# 03-MCU.net
KiCad netlist of a schematic drawn in Altium Designer
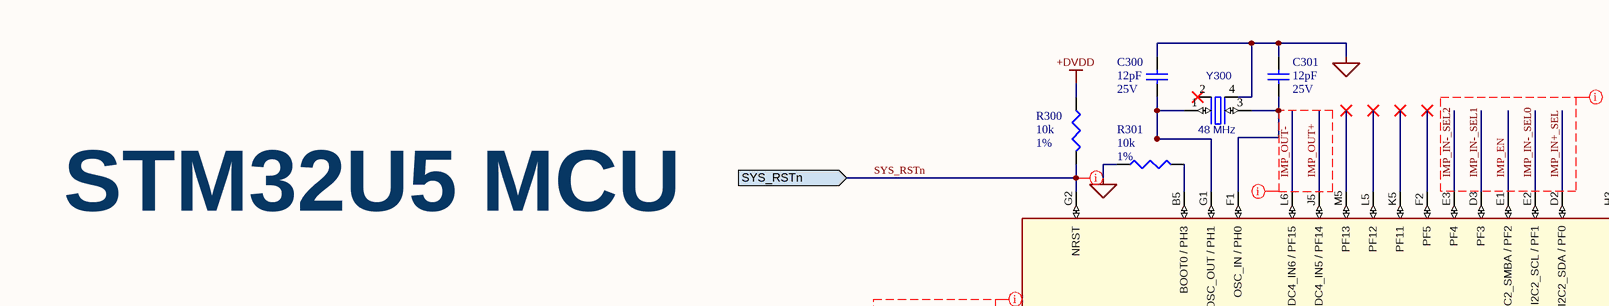
[diagram p0: 03-MCU.SchDoc, top left]
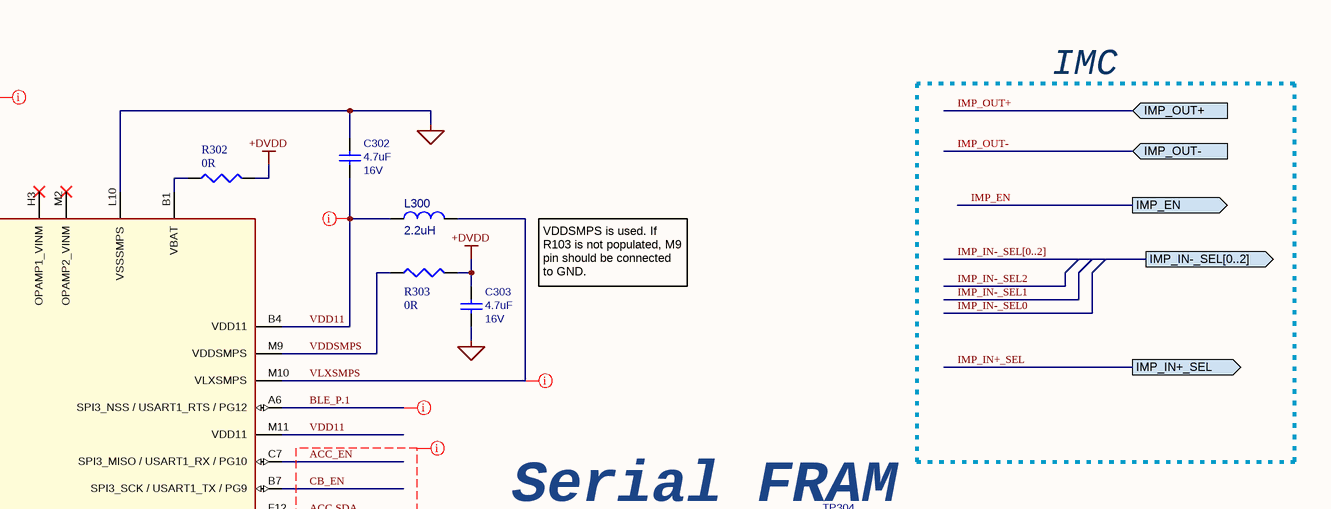
[diagram p1: 03-MCU.SchDoc, top right]
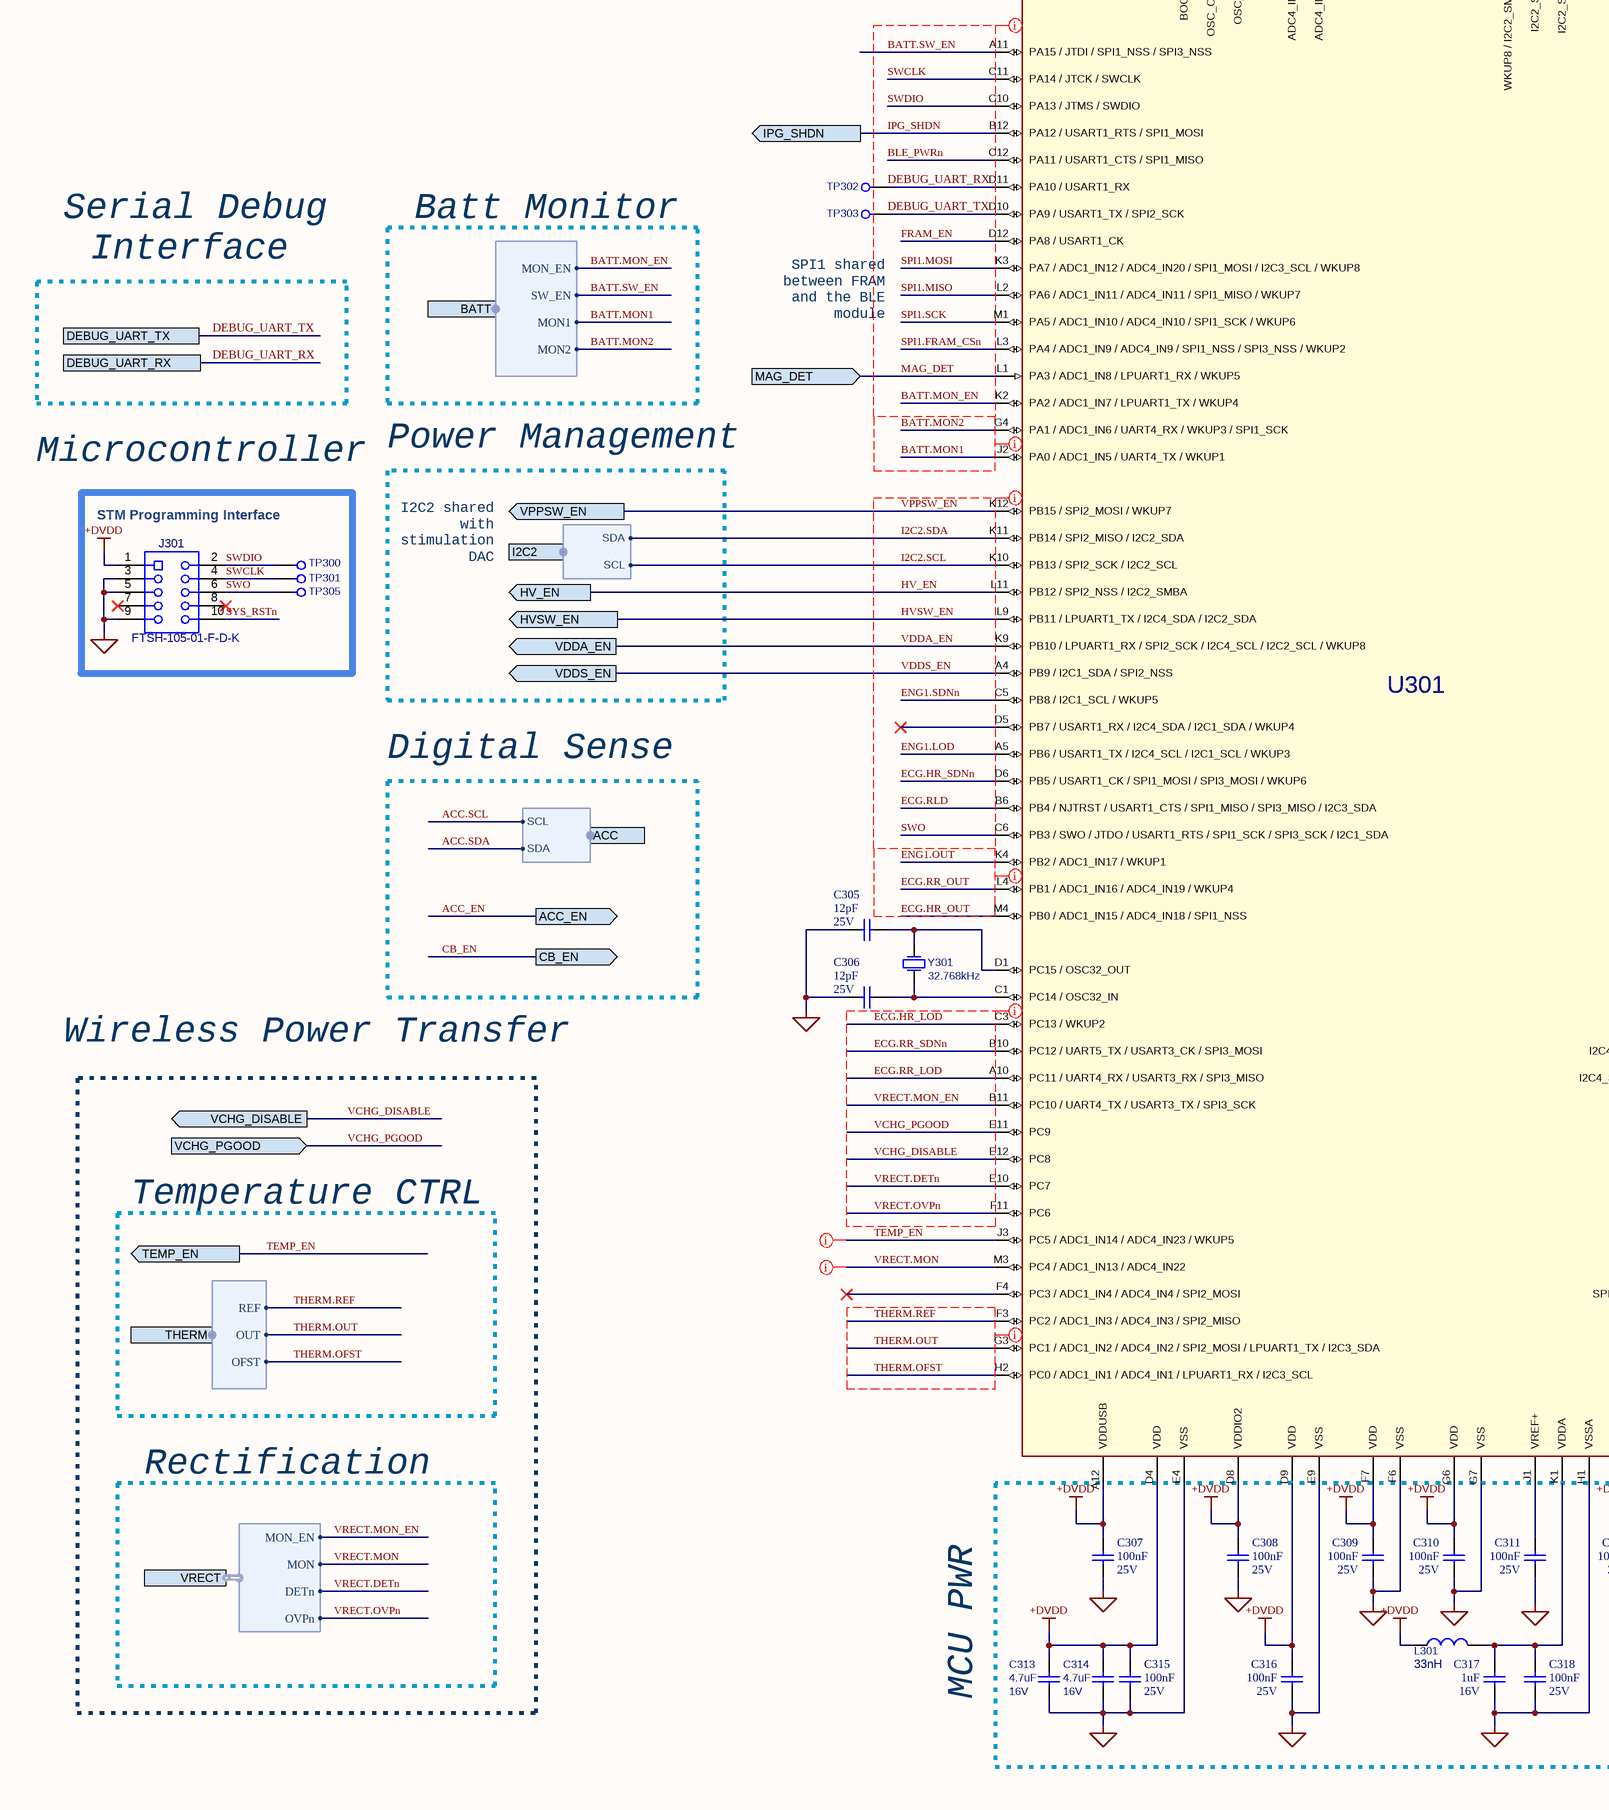
[diagram p2: 03-MCU.SchDoc, bottom left]
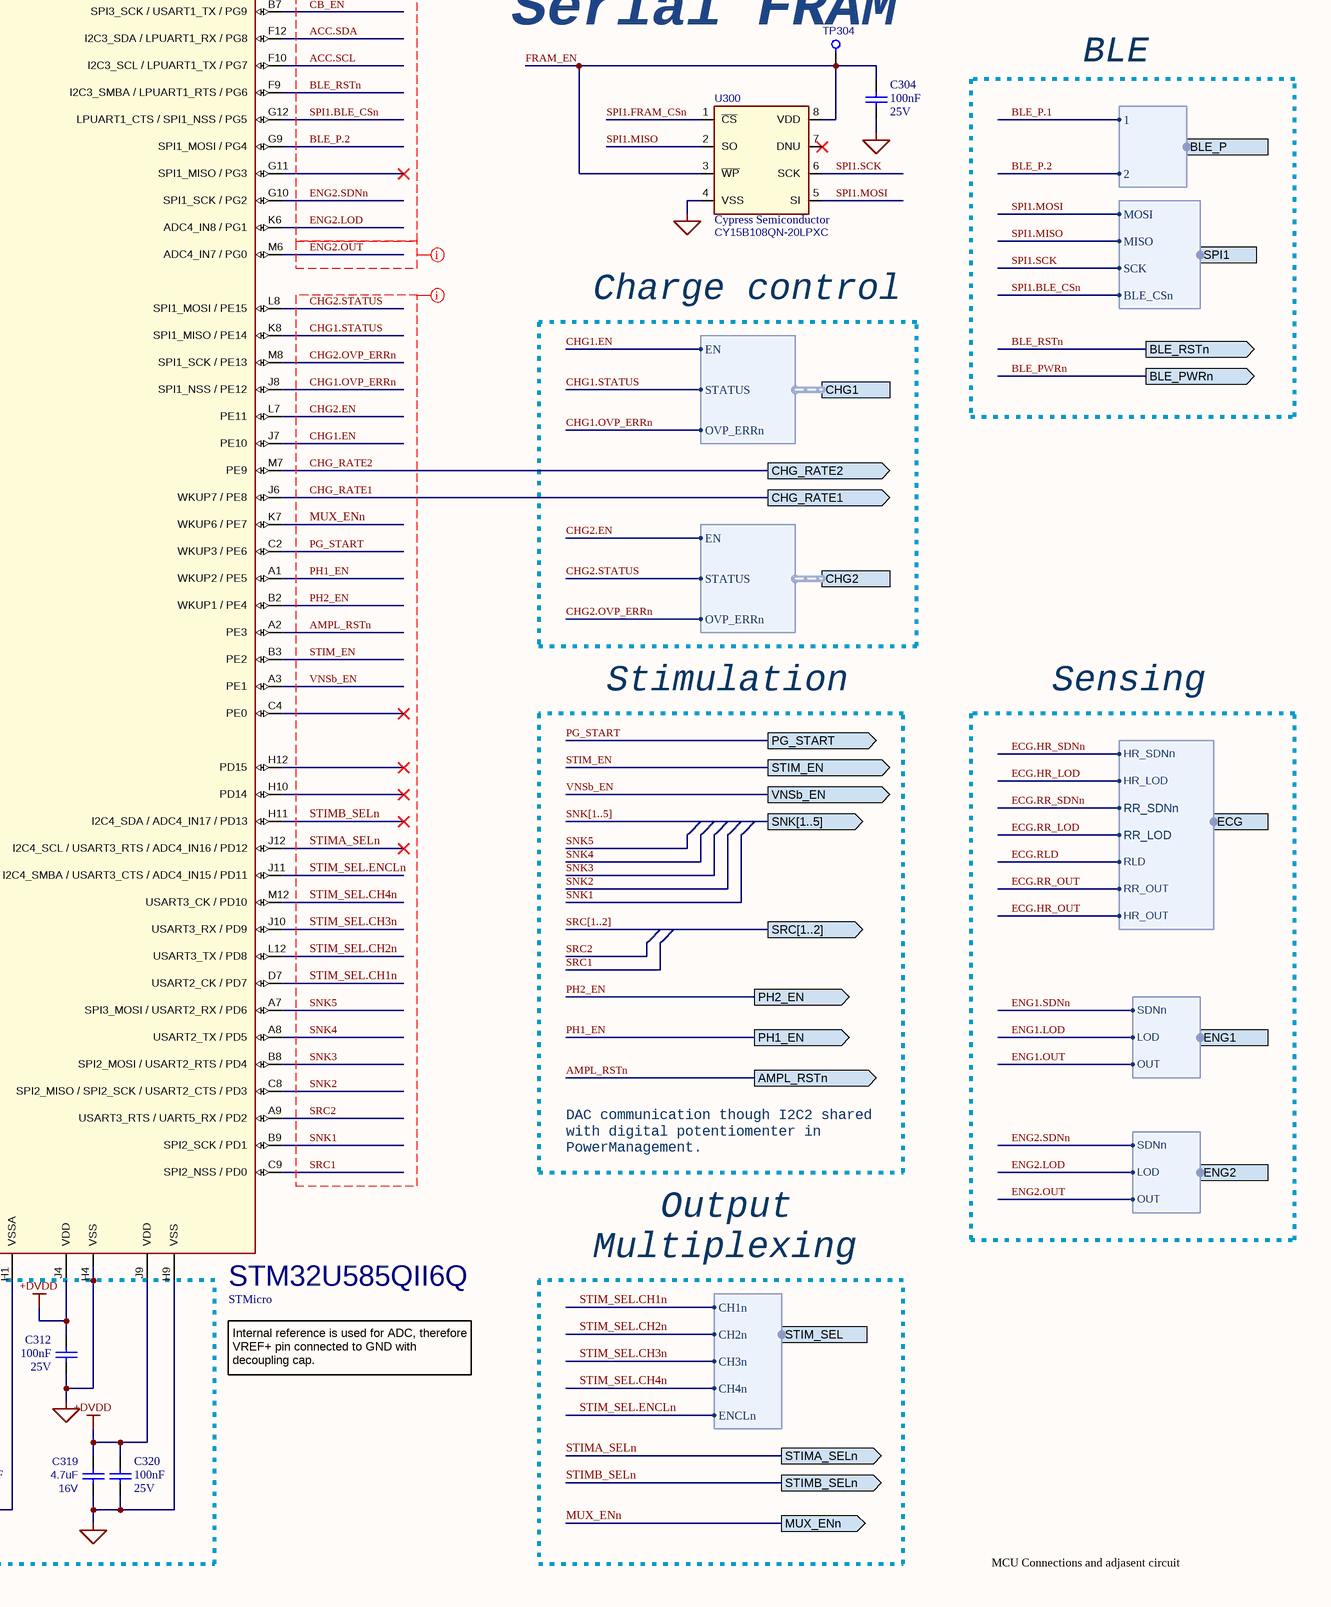
[diagram p3: 03-MCU.SchDoc, bottom right]

(export (version "E")
  (design (tool "Eeschema 10.0.6"))
  (components
    (comp (ref "C300")
      (value "12pF")
      (footprint "C0201_C")
      (fields
        (field (name "MANUFACTURER") "Murata")
        (field (name "MANUFACTURER PART NUMBER") "GRM0335C1E120JA01D")
        (field (name "RATED DC VOLTAGE (URDC)") "25V")
      )
      (libsource (lib "MP-LIBRARY") (part "GRM0335C1E120JA01D"))
    )
    (comp (ref "C301")
      (value "12pF")
      (footprint "C0201_C")
      (fields
        (field (name "MANUFACTURER") "Murata")
        (field (name "MANUFACTURER PART NUMBER") "GRM0335C1E120JA01D")
        (field (name "RATED DC VOLTAGE (URDC)") "25V")
      )
      (libsource (lib "MP-LIBRARY") (part "GRM0335C1E120JA01D"))
    )
    (comp (ref "C302")
      (value "4.7uF")
      (footprint "CAP0603_REDUCED")
      (description "Capacitor, 4.7uF, X5R, 16V, 10%, 0603, Implant-grade")
      (fields
        (field (name "MANUFACTURER") "Murata")
        (field (name "RATING") "16V")
        (field (name "MANUFACTURER PART NUMBER") "GRM188R61C475KE11")
      )
      (libsource (lib "MP-LIBRARY") (part "GRM188R61C475KE11"))
    )
    (comp (ref "C303")
      (value "4.7uF")
      (footprint "CAP0603_REDUCED")
      (description "Capacitor, 4.7uF, X5R, 16V, 10%, 0603, Implant-grade")
      (fields
        (field (name "MANUFACTURER") "Murata")
        (field (name "RATING") "16V")
        (field (name "MANUFACTURER PART NUMBER") "GRM188R61C475KE11")
      )
      (libsource (lib "MP-LIBRARY") (part "GRM188R61C475KE11"))
    )
    (comp (ref "C304")
      (value "100nF")
      (footprint "C0201_C")
      (fields
        (field (name "MANUFACTURER") "Murata")
        (field (name "MANUFACTURER PART NUMBER") "GRM033R61E104KE14J")
        (field (name "RATED DC VOLTAGE (URDC)") "25V")
      )
      (libsource (lib "MP-LIBRARY") (part "GRM033R61E104KE14J"))
    )
    (comp (ref "C305")
      (value "12pF")
      (footprint "C0201_C")
      (fields
        (field (name "MANUFACTURER") "Murata")
        (field (name "MANUFACTURER PART NUMBER") "GRM0335C1E120JA01D")
        (field (name "RATED DC VOLTAGE (URDC)") "25V")
      )
      (libsource (lib "MP-LIBRARY") (part "GRM0335C1E120JA01D"))
    )
    (comp (ref "C306")
      (value "12pF")
      (footprint "C0201_C")
      (fields
        (field (name "MANUFACTURER") "Murata")
        (field (name "MANUFACTURER PART NUMBER") "GRM0335C1E120JA01D")
        (field (name "RATED DC VOLTAGE (URDC)") "25V")
      )
      (libsource (lib "MP-LIBRARY") (part "GRM0335C1E120JA01D"))
    )
    (comp (ref "C307")
      (value "100nF")
      (footprint "C0201_C")
      (fields
        (field (name "MANUFACTURER") "Murata")
        (field (name "MANUFACTURER PART NUMBER") "GRM033R61E104KE14J")
        (field (name "RATED DC VOLTAGE (URDC)") "25V")
      )
      (libsource (lib "MP-LIBRARY") (part "GRM033R61E104KE14J"))
    )
    (comp (ref "C308")
      (value "100nF")
      (footprint "C0201_C")
      (fields
        (field (name "MANUFACTURER") "Murata")
        (field (name "MANUFACTURER PART NUMBER") "GRM033R61E104KE14J")
        (field (name "RATED DC VOLTAGE (URDC)") "25V")
      )
      (libsource (lib "MP-LIBRARY") (part "GRM033R61E104KE14J"))
    )
    (comp (ref "C309")
      (value "100nF")
      (footprint "C0201_C")
      (fields
        (field (name "MANUFACTURER") "Murata")
        (field (name "MANUFACTURER PART NUMBER") "GRM033R61E104KE14J")
        (field (name "RATED DC VOLTAGE (URDC)") "25V")
      )
      (libsource (lib "MP-LIBRARY") (part "GRM033R61E104KE14J"))
    )
    (comp (ref "C310")
      (value "100nF")
      (footprint "C0201_C")
      (fields
        (field (name "MANUFACTURER") "Murata")
        (field (name "MANUFACTURER PART NUMBER") "GRM033R61E104KE14J")
        (field (name "RATED DC VOLTAGE (URDC)") "25V")
      )
      (libsource (lib "MP-LIBRARY") (part "GRM033R61E104KE14J"))
    )
    (comp (ref "C311")
      (value "100nF")
      (footprint "C0201_C")
      (fields
        (field (name "MANUFACTURER") "Murata")
        (field (name "MANUFACTURER PART NUMBER") "GRM033R61E104KE14J")
        (field (name "RATED DC VOLTAGE (URDC)") "25V")
      )
      (libsource (lib "MP-LIBRARY") (part "GRM033R61E104KE14J"))
    )
    (comp (ref "C312")
      (value "100nF")
      (footprint "C0201_C")
      (fields
        (field (name "MANUFACTURER") "Murata")
        (field (name "MANUFACTURER PART NUMBER") "GRM033R61E104KE14J")
        (field (name "RATED DC VOLTAGE (URDC)") "25V")
      )
      (libsource (lib "MP-LIBRARY") (part "GRM033R61E104KE14J"))
    )
    (comp (ref "C313")
      (value "4.7uF")
      (footprint "CAP0603_REDUCED")
      (description "Capacitor, 4.7uF, X5R, 16V, 10%, 0603, Implant-grade")
      (fields
        (field (name "MANUFACTURER") "Murata")
        (field (name "RATING") "16V")
        (field (name "MANUFACTURER PART NUMBER") "GRM188R61C475KE11")
      )
      (libsource (lib "MP-LIBRARY") (part "GRM188R61C475KE11"))
    )
    (comp (ref "C314")
      (value "4.7uF")
      (footprint "CAP0603_REDUCED")
      (description "Capacitor, 4.7uF, X5R, 16V, 10%, 0603, Implant-grade")
      (fields
        (field (name "MANUFACTURER") "Murata")
        (field (name "RATING") "16V")
        (field (name "MANUFACTURER PART NUMBER") "GRM188R61C475KE11")
      )
      (libsource (lib "MP-LIBRARY") (part "GRM188R61C475KE11"))
    )
    (comp (ref "C315")
      (value "100nF")
      (footprint "C0201_C")
      (fields
        (field (name "MANUFACTURER") "Murata")
        (field (name "MANUFACTURER PART NUMBER") "GRM033R61E104KE14J")
        (field (name "RATED DC VOLTAGE (URDC)") "25V")
      )
      (libsource (lib "MP-LIBRARY") (part "GRM033R61E104KE14J"))
    )
    (comp (ref "C316")
      (value "100nF")
      (footprint "C0201_C")
      (fields
        (field (name "MANUFACTURER") "Murata")
        (field (name "MANUFACTURER PART NUMBER") "GRM033R61E104KE14J")
        (field (name "RATED DC VOLTAGE (URDC)") "25V")
      )
      (libsource (lib "MP-LIBRARY") (part "GRM033R61E104KE14J"))
    )
    (comp (ref "C317")
      (value "1uF")
      (footprint "C0201_C")
      (fields
        (field (name "MANUFACTURER") "Murata")
        (field (name "MANUFACTURER PART NUMBER") "GRM033R61C105ME15D")
        (field (name "RATED DC VOLTAGE (URDC)") "16V")
      )
      (libsource (lib "MP-LIBRARY") (part "GRM033R61C105ME15D"))
    )
    (comp (ref "C318")
      (value "100nF")
      (footprint "C0201_C")
      (fields
        (field (name "MANUFACTURER") "Murata")
        (field (name "MANUFACTURER PART NUMBER") "GRM033R61E104KE14J")
        (field (name "RATED DC VOLTAGE (URDC)") "25V")
      )
      (libsource (lib "MP-LIBRARY") (part "GRM033R61E104KE14J"))
    )
    (comp (ref "C319")
      (value "4.7uF")
      (footprint "CAP0603_REDUCED")
      (description "Capacitor, 4.7uF, X5R, 16V, 10%, 0603, Implant-grade")
      (fields
        (field (name "MANUFACTURER") "Murata")
        (field (name "RATING") "16V")
        (field (name "MANUFACTURER PART NUMBER") "GRM188R61C475KE11")
      )
      (libsource (lib "MP-LIBRARY") (part "GRM188R61C475KE11"))
    )
    (comp (ref "C320")
      (value "100nF")
      (footprint "C0201_C")
      (fields
        (field (name "MANUFACTURER") "Murata")
        (field (name "MANUFACTURER PART NUMBER") "GRM033R61E104KE14J")
        (field (name "RATED DC VOLTAGE (URDC)") "25V")
      )
      (libsource (lib "MP-LIBRARY") (part "GRM033R61E104KE14J"))
    )
    (comp (ref "J301")
      (value "FTSH-105-01-F-D-K")
      (footprint "SAMTEC_FTSH-105-01-XXX-D-K")
      (description "Connector, 1.27 mm, 2x5, Male, TH")
      (fields (field (name "MANUFACTURER") "Samtec"))
      (libsource (lib "MP-LIBRARY") (part "FTSH-105-01-F-D-K"))
    )
    (comp (ref "L300")
      (value "2.2uH")
      (footprint "TDK_VLS252010HBX-1")
      (description "Inductor, 2.2uH, 1.76A, 1008")
      (fields
        (field (name "MANUFACTURER") "TDK")
        (field (name "MANUFACTURER PART NUMBER") "VLS252010HBX-2R2M-1")
      )
      (libsource (lib "MP-LIBRARY") (part "VLS252010HBX-2R2M-1"))
    )
    (comp (ref "L301")
      (value "33nH")
      (footprint "L0402_C")
      (description "Inductor, Unshielded, 33nH, 350mA, 0402")
      (fields
        (field (name "MANUFACTURER") "Murata")
        (field (name "MANUFACTURER PART NUMBER") "LQG15HS33NJ02D")
      )
      (libsource (lib "MP-LIBRARY") (part "LQG15HS33NJ02D"))
    )
    (comp (ref "R300")
      (value "10k")
      (footprint "R0201_C")
      (fields
        (field (name "MANUFACTURER") "Vishay")
        (field (name "MANUFACTURER PART NUMBER") "CRCW020110K0FNED")
        (field (name "TOLERANCE") "1%")
        (field (name "POWER") "50mW")
      )
      (libsource (lib "MP-LIBRARY") (part "CRCW020110K0FNED"))
    )
    (comp (ref "R301")
      (value "10k")
      (footprint "R0201_C")
      (fields
        (field (name "MANUFACTURER") "Vishay")
        (field (name "MANUFACTURER PART NUMBER") "CRCW020110K0FNED")
        (field (name "TOLERANCE") "1%")
        (field (name "POWER") "50mW")
      )
      (libsource (lib "MP-LIBRARY") (part "CRCW020110K0FNED"))
    )
    (comp (ref "R302")
      (value "0R")
      (footprint "R0201_C")
      (description "Fixed Resistor, Metal Glaze/thick Film, 0.05W, 0ohm, Surface Mount, 0201")
      (fields
        (field (name "MANUFACTURER") "Vishay")
        (field (name "MANUFACTURER PART NUMBER") "CRCW02010000Z0ED")
      )
      (libsource (lib "MP-LIBRARY") (part "CRCW02010000Z0ED"))
    )
    (comp (ref "R303")
      (value "0R")
      (footprint "R0201_C")
      (description "Fixed Resistor, Metal Glaze/thick Film, 0.05W, 0ohm, Surface Mount, 0201")
      (fields
        (field (name "MANUFACTURER") "Vishay")
        (field (name "MANUFACTURER PART NUMBER") "CRCW02010000Z0ED")
      )
      (libsource (lib "MP-LIBRARY") (part "CRCW02010000Z0ED"))
    )
    (comp (ref "TP300")
      (value "Test Point")
      (footprint "testpad_0.9mm")
      (description "Test pad, 0.90mm circular pad")
      (libsource (lib "MP-LIBRARY") (part "Test Point"))
    )
    (comp (ref "TP301")
      (value "Test Point")
      (footprint "testpad_0.9mm")
      (description "Test pad, 0.90mm circular pad")
      (libsource (lib "MP-LIBRARY") (part "Test Point"))
    )
    (comp (ref "TP302")
      (value "Test Point")
      (footprint "testpad_0.9mm")
      (description "Test pad, 0.90mm circular pad")
      (libsource (lib "MP-LIBRARY") (part "Test Point"))
    )
    (comp (ref "TP303")
      (value "Test Point")
      (footprint "testpad_0.9mm")
      (description "Test pad, 0.90mm circular pad")
      (libsource (lib "MP-LIBRARY") (part "Test Point"))
    )
    (comp (ref "TP304")
      (value "Test Point")
      (footprint "testpad_0.9mm")
      (description "Test pad, 0.90mm circular pad")
      (libsource (lib "MP-LIBRARY") (part "Test Point"))
    )
    (comp (ref "TP305")
      (value "Test Point")
      (footprint "testpad_0.9mm")
      (description "Test pad, 0.90mm circular pad")
      (libsource (lib "MP-LIBRARY") (part "Test Point"))
    )
    (comp (ref "U300")
      (value "CY15B108QN-20LPXC")
      (footprint "CY_002-18131_GQFN8")
      (description "FRAM, 8 Mbit (1024k x 8), SPI, 1.8-3.6V, QFN-8")
      (fields (field (name "MANUFACTURER") "Cypress Semiconductor"))
      (libsource (lib "MP-LIBRARY") (part "CY15B108QN-20LPXC"))
    )
    (comp (ref "U301")
      (value "STM32U585QII6Q")
      (footprint "STM_UFBGA132")
      (fields (field (name "MANUFACTURER") "STMicro"))
      (libsource (lib "MP-LIBRARY") (part "STM32U585QII6Q"))
    )
    (comp (ref "Y300")
      (value "48 MHz")
      (footprint "XTAL_ECS-SMD-CRYSTAL-10-48-CKY-TR")
      (description "48 MHz Â±10ppm Crystal 10pF 100 Ohms 4-SMD, No Lead")
      (fields
        (field (name "MANUFACTURER") "ECS Inc.")
        (field (name "MANUFACTURER PART NUMBER") "ECS-480-10-48-CKY-TR")
      )
      (libsource (lib "MP-LIBRARY") (part "ECS-480-10-48-CKY-TR"))
    )
    (comp (ref "Y301")
      (value "32.768kHz")
      (footprint "MICROCRYSTAL_CC8V-T1A")
      (description "CRYSTAL 32.7680KHZ 6PF SMD")
      (fields
        (field (name "MANUFACTURER") "Micro Crystal")
        (field (name "MANUFACTURER PART NUMBER") "CM8V-T1A-32.768KHZ-6PF-20PPM-TA-QC")
      )
      (libsource (lib "MP-LIBRARY") (part "CM8V-T1A-32.768KHZ-6PF-20PPM-TA-QC"))
    )
  )
  (nets
    (net (code "13") (name "+DVDD") (class "Default")
      (node (ref "C303") (pin "1") (pinfunction "1_1") (pintype "passive"))
      (node (ref "C307") (pin "2") (pinfunction "2_2") (pintype "passive"))
      (node (ref "C308") (pin "2") (pinfunction "2_2") (pintype "passive"))
      (node (ref "C309") (pin "2") (pinfunction "2_2") (pintype "passive"))
      (node (ref "C310") (pin "2") (pinfunction "2_2") (pintype "passive"))
      (node (ref "C312") (pin "2") (pinfunction "2_2") (pintype "passive"))
      (node (ref "C313") (pin "1") (pinfunction "1_1") (pintype "passive"))
      (node (ref "C314") (pin "1") (pinfunction "1_1") (pintype "passive"))
      (node (ref "C315") (pin "2") (pinfunction "2_2") (pintype "passive"))
      (node (ref "C316") (pin "2") (pinfunction "2_2") (pintype "passive"))
      (node (ref "C319") (pin "1") (pinfunction "1_1") (pintype "passive"))
      (node (ref "C320") (pin "2") (pinfunction "2_2") (pintype "passive"))
      (node (ref "J301") (pin "1") (pinfunction "1_1") (pintype "passive"))
      (node (ref "L301") (pin "1") (pinfunction "1_1") (pintype "passive"))
      (node (ref "R300") (pin "1") (pinfunction "1_1") (pintype "passive"))
      (node (ref "R302") (pin "2") (pinfunction "2_2") (pintype "passive"))
      (node (ref "R303") (pin "2") (pinfunction "2_2") (pintype "passive"))
      (node (ref "U301") (pin "A12") (pinfunction "VDDUSB_A12") (pintype "power_in"))
      (node (ref "U301") (pin "D4") (pinfunction "VDD_D4") (pintype "power_in"))
      (node (ref "U301") (pin "D8") (pinfunction "VDDIO2_D8") (pintype "power_in"))
      (node (ref "U301") (pin "D9") (pinfunction "VDD_D9") (pintype "power_in"))
      (node (ref "U301") (pin "F7") (pinfunction "VDD_F7") (pintype "power_in"))
      (node (ref "U301") (pin "G6") (pinfunction "VDD_G6") (pintype "power_in"))
      (node (ref "U301") (pin "J4") (pinfunction "VDD_J4") (pintype "power_in"))
      (node (ref "U301") (pin "J9") (pinfunction "VDD_J9") (pintype "power_in"))
    )
    (net (code "14") (name "/ACC.SCL") (class "Default")
      (node (ref "U301") (pin "F10") (pinfunction "I2C3_SCL_/_LPUART1_TX_/_PG7_F10") (pintype "bidirectional"))
    )
    (net (code "15") (name "/ACC.SDA") (class "Default")
      (node (ref "U301") (pin "F12") (pinfunction "I2C3_SDA_/_LPUART1_RX_/_PG8_F12") (pintype "bidirectional"))
    )
    (net (code "16") (name "/ACC_EN") (class "Default")
      (node (ref "U301") (pin "C7") (pinfunction "SPI3_MISO_/_USART1_RX_/_PG10_C7") (pintype "bidirectional"))
    )
    (net (code "17") (name "/AMPL_RSTn") (class "Default")
      (node (ref "U301") (pin "A2") (pinfunction "PE3_A2") (pintype "bidirectional"))
    )
    (net (code "18") (name "/BATT.MON1") (class "Default")
      (node (ref "U301") (pin "J2") (pinfunction "PA0_/_ADC1_IN5_/_UART4_TX_/_WKUP1_J2") (pintype "bidirectional"))
    )
    (net (code "19") (name "/BATT.MON2") (class "Default")
      (node (ref "U301") (pin "G4") (pinfunction "PA1_/_ADC1_IN6_/_UART4_RX_/_WKUP3_/_SPI1_SCK_G4") (pintype "bidirectional"))
    )
    (net (code "20") (name "/BATT.MON_EN") (class "Default")
      (node (ref "U301") (pin "K2") (pinfunction "PA2_/_ADC1_IN7_/_LPUART1_TX_/_WKUP4_K2") (pintype "bidirectional"))
    )
    (net (code "21") (name "/BATT.SW_EN") (class "Default")
      (node (ref "U301") (pin "A11") (pinfunction "PA15_/_JTDI_/_SPI1_NSS_/_SPI3_NSS_A11") (pintype "bidirectional"))
    )
    (net (code "22") (name "/BLE_P.1") (class "Default")
      (node (ref "U301") (pin "A6") (pinfunction "SPI3_NSS_/_USART1_RTS_/_PG12_A6") (pintype "bidirectional"))
    )
    (net (code "23") (name "/BLE_P.2") (class "Default")
      (node (ref "U301") (pin "G9") (pinfunction "SPI1_MOSI_/_PG4_G9") (pintype "bidirectional"))
    )
    (net (code "24") (name "/BLE_PWRn") (class "Default")
      (node (ref "U301") (pin "C12") (pinfunction "PA11_/_USART1_CTS_/_SPI1_MISO_C12") (pintype "bidirectional"))
    )
    (net (code "25") (name "/BLE_RSTn") (class "Default")
      (node (ref "U301") (pin "F9") (pinfunction "I2C3_SMBA_/_LPUART1_RTS_/_PG6_F9") (pintype "bidirectional"))
    )
    (net (code "26") (name "/CB_EN") (class "Default")
      (node (ref "U301") (pin "B7") (pinfunction "SPI3_SCK_/_USART1_TX_/_PG9_B7") (pintype "bidirectional"))
    )
    (net (code "27") (name "/CHG1.EN") (class "Default")
      (node (ref "U301") (pin "J7") (pinfunction "PE10_J7") (pintype "bidirectional"))
    )
    (net (code "28") (name "/CHG1.OVP_ERRn") (class "Default")
      (node (ref "U301") (pin "J8") (pinfunction "SPI1_NSS_/_PE12_J8") (pintype "bidirectional"))
    )
    (net (code "29") (name "/CHG1.STATUS") (class "Default")
      (node (ref "U301") (pin "K8") (pinfunction "SPI1_MISO_/_PE14_K8") (pintype "bidirectional"))
    )
    (net (code "30") (name "/CHG2.EN") (class "Default")
      (node (ref "U301") (pin "L7") (pinfunction "PE11_L7") (pintype "bidirectional"))
    )
    (net (code "31") (name "/CHG2.OVP_ERRn") (class "Default")
      (node (ref "U301") (pin "M8") (pinfunction "SPI1_SCK_/_PE13_M8") (pintype "bidirectional"))
    )
    (net (code "32") (name "/CHG2.STATUS") (class "Default")
      (node (ref "U301") (pin "L8") (pinfunction "SPI1_MOSI_/_PE15_L8") (pintype "bidirectional"))
    )
    (net (code "33") (name "/CHG_RATE1") (class "Default")
      (node (ref "U301") (pin "J6") (pinfunction "WKUP7_/_PE8_J6") (pintype "bidirectional"))
    )
    (net (code "34") (name "/CHG_RATE2") (class "Default")
      (node (ref "U301") (pin "M7") (pinfunction "PE9_M7") (pintype "bidirectional"))
    )
    (net (code "35") (name "/DEBUG_UART_RX") (class "Default")
      (node (ref "TP302") (pin "1") (pinfunction "1_1") (pintype "passive"))
      (node (ref "U301") (pin "D11") (pinfunction "PA10_/_USART1_RX_D11") (pintype "bidirectional"))
    )
    (net (code "36") (name "/DEBUG_UART_TX") (class "Default")
      (node (ref "TP303") (pin "1") (pinfunction "1_1") (pintype "passive"))
      (node (ref "U301") (pin "D10") (pinfunction "PA9_/_USART1_TX_/_SPI2_SCK_D10") (pintype "bidirectional"))
    )
    (net (code "37") (name "/ECG.HR_LOD") (class "Default")
      (node (ref "U301") (pin "C3") (pinfunction "PC13_/_WKUP2_C3") (pintype "bidirectional"))
    )
    (net (code "38") (name "/ECG.HR_OUT") (class "Default")
      (node (ref "U301") (pin "M4") (pinfunction "PB0_/_ADC1_IN15_/_ADC4_IN18_/_SPI1_NSS_M4") (pintype "bidirectional"))
    )
    (net (code "39") (name "/ECG.HR_SDNn") (class "Default")
      (node (ref "U301") (pin "D6") (pinfunction "PB5_/_USART1_CK_/_SPI1_MOSI_/_SPI3_MOSI_/_WKUP6_D6") (pintype "bidirectional"))
    )
    (net (code "40") (name "/ECG.RLD") (class "Default")
      (node (ref "U301") (pin "B6") (pinfunction "PB4_/_NJTRST_/_USART1_CTS_/_SPI1_MISO_/_SPI3_MISO_/_I2C3_SDA_B6") (pintype "bidirectional"))
    )
    (net (code "41") (name "/ECG.RR_LOD") (class "Default")
      (node (ref "U301") (pin "A10") (pinfunction "PC11_/_UART4_RX_/_USART3_RX_/_SPI3_MISO_A10") (pintype "bidirectional"))
    )
    (net (code "42") (name "/ECG.RR_OUT") (class "Default")
      (node (ref "U301") (pin "L4") (pinfunction "PB1_/_ADC1_IN16_/_ADC4_IN19_/_WKUP4_L4") (pintype "bidirectional"))
    )
    (net (code "43") (name "/ECG.RR_SDNn") (class "Default")
      (node (ref "U301") (pin "B10") (pinfunction "PC12_/_UART5_TX_/_USART3_CK_/_SPI3_MOSI_B10") (pintype "bidirectional"))
    )
    (net (code "44") (name "/ENG1.LOD") (class "Default")
      (node (ref "U301") (pin "A5") (pinfunction "PB6_/_USART1_TX_/_I2C4_SCL_/_I2C1_SCL_/_WKUP3_A5") (pintype "bidirectional"))
    )
    (net (code "45") (name "/ENG1.OUT") (class "Default")
      (node (ref "U301") (pin "K4") (pinfunction "PB2_/_ADC1_IN17_/_WKUP1_K4") (pintype "bidirectional"))
    )
    (net (code "46") (name "/ENG1.SDNn") (class "Default")
      (node (ref "U301") (pin "C5") (pinfunction "PB8_/_I2C1_SCL_/_WKUP5_C5") (pintype "bidirectional"))
    )
    (net (code "47") (name "/ENG2.LOD") (class "Default")
      (node (ref "U301") (pin "K6") (pinfunction "ADC4_IN8_/_PG1_K6") (pintype "bidirectional"))
    )
    (net (code "48") (name "/ENG2.OUT") (class "Default")
      (node (ref "U301") (pin "M6") (pinfunction "ADC4_IN7_/_PG0_M6") (pintype "bidirectional"))
    )
    (net (code "49") (name "/ENG2.SDNn") (class "Default")
      (node (ref "U301") (pin "G10") (pinfunction "SPI1_SCK_/_PG2_G10") (pintype "bidirectional"))
    )
    (net (code "50") (name "/FRAM_EN") (class "Default")
      (node (ref "C304") (pin "2") (pinfunction "2_2") (pintype "passive"))
      (node (ref "TP304") (pin "1") (pinfunction "1_1") (pintype "passive"))
      (node (ref "U300") (pin "3") (pinfunction "~{WP}_3") (pintype "passive"))
      (node (ref "U300") (pin "8") (pinfunction "VDD_8") (pintype "power_in"))
      (node (ref "U301") (pin "D12") (pinfunction "PA8_/_USART1_CK_D12") (pintype "bidirectional"))
    )
    (net (code "51") (name "/HVSW_EN") (class "Default")
      (node (ref "U301") (pin "L9") (pinfunction "PB11_/_LPUART1_TX_/_I2C4_SDA_/_I2C2_SDA_L9") (pintype "bidirectional"))
    )
    (net (code "52") (name "/HV_EN") (class "Default")
      (node (ref "U301") (pin "L11") (pinfunction "PB12_/_SPI2_NSS_/_I2C2_SMBA_L11") (pintype "bidirectional"))
    )
    (net (code "53") (name "/I2C2.SCL") (class "Default")
      (node (ref "U301") (pin "K10") (pinfunction "PB13_/_SPI2_SCK_/_I2C2_SCL_K10") (pintype "bidirectional"))
    )
    (net (code "54") (name "/I2C2.SDA") (class "Default")
      (node (ref "U301") (pin "K11") (pinfunction "PB14_/_SPI2_MISO_/_I2C2_SDA_K11") (pintype "bidirectional"))
    )
    (net (code "55") (name "/IMP_EN") (class "Default")
      (node (ref "U301") (pin "E1") (pinfunction "WKUP8_/_I2C2_SMBA_/_PF2_E1") (pintype "bidirectional"))
    )
    (net (code "56") (name "/IMP_IN+_SEL") (class "Default")
      (node (ref "U301") (pin "D2") (pinfunction "I2C2_SDA_/_PF0_D2") (pintype "bidirectional"))
    )
    (net (code "57") (name "/IMP_IN-_SEL0") (class "Default")
      (node (ref "U301") (pin "E2") (pinfunction "I2C2_SCL_/_PF1_E2") (pintype "bidirectional"))
    )
    (net (code "58") (name "/IMP_IN-_SEL1") (class "Default")
      (node (ref "U301") (pin "D3") (pinfunction "PF3_D3") (pintype "bidirectional"))
    )
    (net (code "59") (name "/IMP_IN-_SEL2") (class "Default")
      (node (ref "U301") (pin "E3") (pinfunction "PF4_E3") (pintype "bidirectional"))
    )
    (net (code "61") (name "/IMP_OUT+") (class "Default")
      (node (ref "U301") (pin "J5") (pinfunction "ADC4_IN5_/_PF14_J5") (pintype "bidirectional"))
    )
    (net (code "62") (name "/IMP_OUT-") (class "Default")
      (node (ref "U301") (pin "L6") (pinfunction "ADC4_IN6_/_PF15_L6") (pintype "bidirectional"))
    )
    (net (code "63") (name "/IPG_SHDN") (class "Default")
      (node (ref "U301") (pin "B12") (pinfunction "PA12_/_USART1_RTS_/_SPI1_MOSI_B12") (pintype "bidirectional"))
    )
    (net (code "64") (name "/MAG_DET") (class "Default")
      (node (ref "U301") (pin "L1") (pinfunction "PA3_/_ADC1_IN8_/_LPUART1_RX_/_WKUP5_L1") (pintype "input"))
    )
    (net (code "65") (name "/MUX_ENn") (class "Default")
      (node (ref "U301") (pin "K7") (pinfunction "WKUP6_/_PE7_K7") (pintype "bidirectional"))
    )
    (net (code "66") (name "/PG_START") (class "Default")
      (node (ref "U301") (pin "C2") (pinfunction "WKUP3_/_PE6_C2") (pintype "bidirectional"))
    )
    (net (code "67") (name "/PH1_EN") (class "Default")
      (node (ref "U301") (pin "A1") (pinfunction "WKUP2_/_PE5_A1") (pintype "bidirectional"))
    )
    (net (code "68") (name "/PH2_EN") (class "Default")
      (node (ref "U301") (pin "B2") (pinfunction "WKUP1_/_PE4_B2") (pintype "bidirectional"))
    )
    (net (code "69") (name "/SNK1") (class "Default")
      (node (ref "U301") (pin "B9") (pinfunction "SPI2_SCK_/_PD1_B9") (pintype "bidirectional"))
    )
    (net (code "70") (name "/SNK2") (class "Default")
      (node (ref "U301") (pin "C8") (pinfunction "SPI2_MISO_/_SPI2_SCK_/_USART2_CTS_/_PD3_C8") (pintype "bidirectional"))
    )
    (net (code "71") (name "/SNK3") (class "Default")
      (node (ref "U301") (pin "B8") (pinfunction "SPI2_MOSI_/_USART2_RTS_/_PD4_B8") (pintype "bidirectional"))
    )
    (net (code "72") (name "/SNK4") (class "Default")
      (node (ref "U301") (pin "A8") (pinfunction "USART2_TX_/_PD5_A8") (pintype "bidirectional"))
    )
    (net (code "73") (name "/SNK5") (class "Default")
      (node (ref "U301") (pin "A7") (pinfunction "SPI3_MOSI_/_USART2_RX_/_PD6_A7") (pintype "bidirectional"))
    )
    (net (code "75") (name "/SPI1.BLE_CSn") (class "Default")
      (node (ref "U301") (pin "G12") (pinfunction "LPUART1_CTS_/_SPI1_NSS_/_PG5_G12") (pintype "bidirectional"))
    )
    (net (code "76") (name "/SPI1.FRAM_CSn") (class "Default")
      (node (ref "U300") (pin "1") (pinfunction "~{CS}_1") (pintype "passive"))
      (node (ref "U301") (pin "L3") (pinfunction "PA4_/_ADC1_IN9_/_ADC4_IN9_/_SPI1_NSS_/_SPI3_NSS_/_WKUP2_L3") (pintype "bidirectional"))
    )
    (net (code "77") (name "/SPI1.MISO") (class "Default")
      (node (ref "U300") (pin "2") (pinfunction "SO_2") (pintype "passive"))
      (node (ref "U301") (pin "L2") (pinfunction "PA6_/_ADC1_IN11_/_ADC4_IN11_/_SPI1_MISO_/_WKUP7_L2") (pintype "bidirectional"))
    )
    (net (code "78") (name "/SPI1.MOSI") (class "Default")
      (node (ref "U300") (pin "5") (pinfunction "SI_5") (pintype "passive"))
      (node (ref "U301") (pin "K3") (pinfunction "PA7_/_ADC1_IN12_/_ADC4_IN20_/_SPI1_MOSI_/_I2C3_SCL_/_WKUP8_K3") (pintype "bidirectional"))
    )
    (net (code "79") (name "/SPI1.SCK") (class "Default")
      (node (ref "U300") (pin "6") (pinfunction "SCK_6") (pintype "passive"))
      (node (ref "U301") (pin "M1") (pinfunction "PA5_/_ADC1_IN10_/_ADC4_IN10_/_SPI1_SCK_/_WKUP6_M1") (pintype "bidirectional"))
    )
    (net (code "80") (name "/SRC1") (class "Default")
      (node (ref "U301") (pin "C9") (pinfunction "SPI2_NSS_/_PD0_C9") (pintype "bidirectional"))
    )
    (net (code "81") (name "/SRC2") (class "Default")
      (node (ref "U301") (pin "A9") (pinfunction "USART3_RTS_/_UART5_RX_/_PD2_A9") (pintype "bidirectional"))
    )
    (net (code "83") (name "/STIMA_SELn") (class "Default")
      (node (ref "U301") (pin "J12") (pinfunction "I2C4_SCL_/_USART3_RTS_/_ADC4_IN16_/_PD12_J12") (pintype "bidirectional+no_connect"))
    )
    (net (code "84") (name "/STIMB_SELn") (class "Default")
      (node (ref "U301") (pin "H11") (pinfunction "I2C4_SDA_/_ADC4_IN17_/_PD13_H11") (pintype "bidirectional+no_connect"))
    )
    (net (code "85") (name "/STIM_EN") (class "Default")
      (node (ref "U301") (pin "B3") (pinfunction "PE2_B3") (pintype "bidirectional"))
    )
    (net (code "86") (name "/STIM_SEL.CH1n") (class "Default")
      (node (ref "U301") (pin "D7") (pinfunction "USART2_CK_/_PD7_D7") (pintype "bidirectional"))
    )
    (net (code "87") (name "/STIM_SEL.CH2n") (class "Default")
      (node (ref "U301") (pin "L12") (pinfunction "USART3_TX_/_PD8_L12") (pintype "bidirectional"))
    )
    (net (code "88") (name "/STIM_SEL.CH3n") (class "Default")
      (node (ref "U301") (pin "J10") (pinfunction "USART3_RX_/_PD9_J10") (pintype "bidirectional"))
    )
    (net (code "89") (name "/STIM_SEL.CH4n") (class "Default")
      (node (ref "U301") (pin "M12") (pinfunction "USART3_CK_/_PD10_M12") (pintype "bidirectional"))
    )
    (net (code "90") (name "/STIM_SEL.ENCLn") (class "Default")
      (node (ref "U301") (pin "J11") (pinfunction "I2C4_SMBA_/_USART3_CTS_/_ADC4_IN15_/_PD11_J11") (pintype "bidirectional"))
    )
    (net (code "91") (name "/SWCLK") (class "Default")
      (node (ref "J301") (pin "4") (pinfunction "4_4") (pintype "passive"))
      (node (ref "TP301") (pin "1") (pinfunction "1_1") (pintype "passive"))
      (node (ref "U301") (pin "C11") (pinfunction "PA14_/_JTCK_/_SWCLK_C11") (pintype "bidirectional"))
    )
    (net (code "92") (name "/SWDIO") (class "Default")
      (node (ref "J301") (pin "2") (pinfunction "2_2") (pintype "passive"))
      (node (ref "TP300") (pin "1") (pinfunction "1_1") (pintype "passive"))
      (node (ref "U301") (pin "C10") (pinfunction "PA13_/_JTMS_/_SWDIO_C10") (pintype "bidirectional"))
    )
    (net (code "93") (name "/SWO") (class "Default")
      (node (ref "J301") (pin "6") (pinfunction "6_6") (pintype "passive"))
      (node (ref "TP305") (pin "1") (pinfunction "1_1") (pintype "passive"))
      (node (ref "U301") (pin "C6") (pinfunction "PB3_/_SWO_/_JTDO_/_USART1_RTS_/_SPI1_SCK_/_SPI3_SCK_/_I2C1_SDA_C6") (pintype "bidirectional"))
    )
    (net (code "94") (name "/SYS_RSTn") (class "Default")
      (node (ref "J301") (pin "10") (pinfunction "10_10") (pintype "passive"))
      (node (ref "R300") (pin "2") (pinfunction "2_2") (pintype "passive"))
      (node (ref "U301") (pin "G2") (pinfunction "NRST_G2") (pintype "bidirectional"))
    )
    (net (code "95") (name "/TEMP_EN") (class "Default")
      (node (ref "U301") (pin "J3") (pinfunction "PC5_/_ADC1_IN14_/_ADC4_IN23_/_WKUP5_J3") (pintype "bidirectional"))
    )
    (net (code "96") (name "/THERM.OFST") (class "Default")
      (node (ref "U301") (pin "H2") (pinfunction "PC0_/_ADC1_IN1_/_ADC4_IN1_/_LPUART1_RX_/_I2C3_SCL_H2") (pintype "bidirectional"))
    )
    (net (code "97") (name "/THERM.OUT") (class "Default")
      (node (ref "U301") (pin "G3") (pinfunction "PC1_/_ADC1_IN2_/_ADC4_IN2_/_SPI2_MOSI_/_LPUART1_TX_/_I2C3_SDA_G3") (pintype "bidirectional"))
    )
    (net (code "98") (name "/THERM.REF") (class "Default")
      (node (ref "U301") (pin "F3") (pinfunction "PC2_/_ADC1_IN3_/_ADC4_IN3_/_SPI2_MISO_F3") (pintype "bidirectional"))
    )
    (net (code "99") (name "/VCHG_DISABLE") (class "Default")
      (node (ref "U301") (pin "E12") (pinfunction "PC8_E12") (pintype "bidirectional"))
    )
    (net (code "100") (name "/VCHG_PGOOD") (class "Default")
      (node (ref "U301") (pin "E11") (pinfunction "PC9_E11") (pintype "bidirectional"))
    )
    (net (code "101") (name "/VDD11") (class "Default")
      (node (ref "C302") (pin "2") (pinfunction "2_2") (pintype "passive"))
      (node (ref "L300") (pin "1") (pinfunction "1_1") (pintype "passive"))
      (node (ref "U301") (pin "B4") (pinfunction "VDD11_B4") (pintype "power_in"))
      (node (ref "U301") (pin "M11") (pinfunction "VDD11_M11") (pintype "power_in"))
    )
    (net (code "102") (name "/VDDA_EN") (class "Default")
      (node (ref "U301") (pin "K9") (pinfunction "PB10_/_LPUART1_RX_/_SPI2_SCK_/_I2C4_SCL_/_I2C2_SCL_/_WKUP8_K9") (pintype "bidirectional"))
    )
    (net (code "103") (name "/VDDSMPS") (class "Default")
      (node (ref "R303") (pin "1") (pinfunction "1_1") (pintype "passive"))
      (node (ref "U301") (pin "M9") (pinfunction "VDDSMPS_M9") (pintype "power_in"))
    )
    (net (code "104") (name "/VDDS_EN") (class "Default")
      (node (ref "U301") (pin "A4") (pinfunction "PB9_/_I2C1_SDA_/_SPI2_NSS_A4") (pintype "bidirectional"))
    )
    (net (code "105") (name "/VLXSMPS") (class "Default")
      (node (ref "L300") (pin "2") (pinfunction "2_2") (pintype "passive"))
      (node (ref "U301") (pin "M10") (pinfunction "VLXSMPS_M10") (pintype "power_in"))
    )
    (net (code "106") (name "/VNSb_EN") (class "Default")
      (node (ref "U301") (pin "A3") (pinfunction "PE1_A3") (pintype "bidirectional"))
    )
    (net (code "107") (name "/VPPSW_EN") (class "Default")
      (node (ref "U301") (pin "K12") (pinfunction "PB15_/_SPI2_MOSI_/_WKUP7_K12") (pintype "bidirectional"))
    )
    (net (code "108") (name "/VRECT.DETn") (class "Default")
      (node (ref "U301") (pin "E10") (pinfunction "PC7_E10") (pintype "bidirectional"))
    )
    (net (code "109") (name "/VRECT.MON") (class "Default")
      (node (ref "U301") (pin "M3") (pinfunction "PC4_/_ADC1_IN13_/_ADC4_IN22_M3") (pintype "bidirectional"))
    )
    (net (code "110") (name "/VRECT.MON_EN") (class "Default")
      (node (ref "U301") (pin "B11") (pinfunction "PC10_/_UART4_TX_/_USART3_TX_/_SPI3_SCK_B11") (pintype "bidirectional"))
    )
    (net (code "111") (name "/VRECT.OVPn") (class "Default")
      (node (ref "U301") (pin "F11") (pinfunction "PC6_F11") (pintype "bidirectional"))
    )
    (net (code "122") (name "GND") (class "Default")
      (node (ref "C300") (pin "1") (pinfunction "1_1") (pintype "passive"))
      (node (ref "C301") (pin "2") (pinfunction "2_2") (pintype "passive"))
      (node (ref "C302") (pin "1") (pinfunction "1_1") (pintype "passive"))
      (node (ref "C303") (pin "2") (pinfunction "2_2") (pintype "passive"))
      (node (ref "C304") (pin "1") (pinfunction "1_1") (pintype "passive"))
      (node (ref "C305") (pin "1") (pinfunction "1_1") (pintype "passive"))
      (node (ref "C306") (pin "1") (pinfunction "1_1") (pintype "passive"))
      (node (ref "C307") (pin "1") (pinfunction "1_1") (pintype "passive"))
      (node (ref "C308") (pin "1") (pinfunction "1_1") (pintype "passive"))
      (node (ref "C309") (pin "1") (pinfunction "1_1") (pintype "passive"))
      (node (ref "C310") (pin "1") (pinfunction "1_1") (pintype "passive"))
      (node (ref "C311") (pin "1") (pinfunction "1_1") (pintype "passive"))
      (node (ref "C312") (pin "1") (pinfunction "1_1") (pintype "passive"))
      (node (ref "C313") (pin "2") (pinfunction "2_2") (pintype "passive"))
      (node (ref "C314") (pin "2") (pinfunction "2_2") (pintype "passive"))
      (node (ref "C315") (pin "1") (pinfunction "1_1") (pintype "passive"))
      (node (ref "C316") (pin "1") (pinfunction "1_1") (pintype "passive"))
      (node (ref "C317") (pin "2") (pinfunction "2_2") (pintype "passive"))
      (node (ref "C318") (pin "1") (pinfunction "1_1") (pintype "passive"))
      (node (ref "C319") (pin "2") (pinfunction "2_2") (pintype "passive"))
      (node (ref "C320") (pin "1") (pinfunction "1_1") (pintype "passive"))
      (node (ref "J301") (pin "3") (pinfunction "3_3") (pintype "passive"))
      (node (ref "J301") (pin "5") (pinfunction "5_5") (pintype "passive"))
      (node (ref "J301") (pin "9") (pinfunction "9_9") (pintype "passive"))
      (node (ref "R301") (pin "1") (pinfunction "1_1") (pintype "passive"))
      (node (ref "U300") (pin "4") (pinfunction "VSS_4") (pintype "power_in"))
      (node (ref "U301") (pin "E4") (pinfunction "VSS_E4") (pintype "power_in"))
      (node (ref "U301") (pin "E9") (pinfunction "VSS_E9") (pintype "power_in"))
      (node (ref "U301") (pin "F6") (pinfunction "VSS_F6") (pintype "power_in"))
      (node (ref "U301") (pin "G7") (pinfunction "VSS_G7") (pintype "power_in"))
      (node (ref "U301") (pin "H1") (pinfunction "VSSA_H1") (pintype "power_in"))
      (node (ref "U301") (pin "H4") (pinfunction "VSS_H4") (pintype "power_in"))
      (node (ref "U301") (pin "H9") (pinfunction "VSS_H9") (pintype "power_in"))
      (node (ref "U301") (pin "L10") (pinfunction "VSSSMPS_L10") (pintype "power_in"))
      (node (ref "Y300") (pin "4") (pinfunction "GND_4") (pintype "passive"))
    )
    (net (code "123") (name "Net-(U301-BOOT0_{slash}_PH3)") (class "Default")
      (node (ref "R301") (pin "2") (pinfunction "2_2") (pintype "passive"))
      (node (ref "U301") (pin "B5") (pinfunction "BOOT0_/_PH3_B5") (pintype "bidirectional"))
    )
    (net (code "124") (name "Net-(U301-OSC_IN_{slash}_PH0)") (class "Default")
      (node (ref "C301") (pin "1") (pinfunction "1_1") (pintype "passive"))
      (node (ref "U301") (pin "F1") (pinfunction "OSC_IN_/_PH0_F1") (pintype "bidirectional"))
      (node (ref "Y300") (pin "3") (pinfunction "OUT/IN_3") (pintype "bidirectional"))
    )
    (net (code "125") (name "Net-(U301-OSC_OUT_{slash}_PH1)") (class "Default")
      (node (ref "C300") (pin "2") (pinfunction "2_2") (pintype "passive"))
      (node (ref "U301") (pin "G1") (pinfunction "OSC_OUT_/_PH1_G1") (pintype "bidirectional"))
      (node (ref "Y300") (pin "1") (pinfunction "IN/OUT_1") (pintype "bidirectional"))
    )
    (net (code "126") (name "Net-(U301-PC14_{slash}_OSC32_IN)") (class "Default")
      (node (ref "C306") (pin "2") (pinfunction "2_2") (pintype "passive"))
      (node (ref "U301") (pin "C1") (pinfunction "PC14_/_OSC32_IN_C1") (pintype "bidirectional"))
      (node (ref "Y301") (pin "1") (pinfunction "1_1") (pintype "passive"))
    )
    (net (code "127") (name "Net-(U301-PC15_{slash}_OSC32_OUT)") (class "Default")
      (node (ref "C305") (pin "2") (pinfunction "2_2") (pintype "passive"))
      (node (ref "U301") (pin "D1") (pinfunction "PC15_/_OSC32_OUT_D1") (pintype "bidirectional"))
      (node (ref "Y301") (pin "2") (pinfunction "2_2") (pintype "passive"))
    )
    (net (code "128") (name "Net-(U301-VBAT)") (class "Default")
      (node (ref "R302") (pin "1") (pinfunction "1_1") (pintype "passive"))
      (node (ref "U301") (pin "B1") (pinfunction "VBAT_B1") (pintype "power_in"))
    )
    (net (code "129") (name "Net-(U301-VDDA)") (class "Default")
      (node (ref "C317") (pin "1") (pinfunction "1_1") (pintype "passive"))
      (node (ref "C318") (pin "2") (pinfunction "2_2") (pintype "passive"))
      (node (ref "L301") (pin "2") (pinfunction "2_2") (pintype "passive"))
      (node (ref "U301") (pin "K1") (pinfunction "VDDA_K1") (pintype "power_in"))
    )
    (net (code "130") (name "Net-(U301-VREF+)") (class "Default")
      (node (ref "C311") (pin "2") (pinfunction "2_2") (pintype "passive"))
      (node (ref "U301") (pin "J1") (pinfunction "VREF+_J1") (pintype "power_in"))
    )
    (net (code "131") (name "unconnected-(J301-Pad7)") (class "Default")
      (node (ref "J301") (pin "7") (pinfunction "7_7") (pintype "passive+no_connect"))
    )
    (net (code "132") (name "unconnected-(J301-Pad8)") (class "Default")
      (node (ref "J301") (pin "8") (pinfunction "8_8") (pintype "passive+no_connect"))
    )
    (net (code "133") (name "unconnected-(U300-DNU-Pad7)") (class "Default")
      (node (ref "U300") (pin "7") (pinfunction "DNU_7") (pintype "passive+no_connect"))
    )
    (net (code "134") (name "unconnected-(U301-OPAMP1_VINM-PadH3)") (class "Default")
      (node (ref "U301") (pin "H3") (pinfunction "OPAMP1_VINM_H3") (pintype "passive+no_connect"))
    )
    (net (code "135") (name "unconnected-(U301-OPAMP2_VINM-PadM2)") (class "Default")
      (node (ref "U301") (pin "M2") (pinfunction "OPAMP2_VINM_M2") (pintype "passive+no_connect"))
    )
    (net (code "136") (name "unconnected-(U301-PB7_{slash}_USART1_RX_{slash}_I2C4_SDA_{slash}_I2C1_SDA_{slash}_WKUP4-PadD5)") (class "Default")
      (node (ref "U301") (pin "D5") (pinfunction "PB7_/_USART1_RX_/_I2C4_SDA_/_I2C1_SDA_/_WKUP4_D5") (pintype "bidirectional+no_connect"))
    )
    (net (code "137") (name "unconnected-(U301-PC3_{slash}_ADC1_IN4_{slash}_ADC4_IN4_{slash}_SPI2_MOSI-PadF4)") (class "Default")
      (node (ref "U301") (pin "F4") (pinfunction "PC3_/_ADC1_IN4_/_ADC4_IN4_/_SPI2_MOSI_F4") (pintype "bidirectional+no_connect"))
    )
    (net (code "138") (name "unconnected-(U301-PD14-PadH10)") (class "Default")
      (node (ref "U301") (pin "H10") (pinfunction "PD14_H10") (pintype "bidirectional+no_connect"))
    )
    (net (code "139") (name "unconnected-(U301-PD15-PadH12)") (class "Default")
      (node (ref "U301") (pin "H12") (pinfunction "PD15_H12") (pintype "bidirectional+no_connect"))
    )
    (net (code "140") (name "unconnected-(U301-PE0-PadC4)") (class "Default")
      (node (ref "U301") (pin "C4") (pinfunction "PE0_C4") (pintype "bidirectional+no_connect"))
    )
    (net (code "141") (name "unconnected-(U301-PF5-PadF2)") (class "Default")
      (node (ref "U301") (pin "F2") (pinfunction "PF5_F2") (pintype "bidirectional+no_connect"))
    )
    (net (code "142") (name "unconnected-(U301-PF11-PadK5)") (class "Default")
      (node (ref "U301") (pin "K5") (pinfunction "PF11_K5") (pintype "bidirectional+no_connect"))
    )
    (net (code "143") (name "unconnected-(U301-PF12-PadL5)") (class "Default")
      (node (ref "U301") (pin "L5") (pinfunction "PF12_L5") (pintype "bidirectional+no_connect"))
    )
    (net (code "144") (name "unconnected-(U301-PF13-PadM5)") (class "Default")
      (node (ref "U301") (pin "M5") (pinfunction "PF13_M5") (pintype "bidirectional+no_connect"))
    )
    (net (code "145") (name "unconnected-(U301-SPI1_MISO_{slash}_PG3-PadG11)") (class "Default")
      (node (ref "U301") (pin "G11") (pinfunction "SPI1_MISO_/_PG3_G11") (pintype "bidirectional+no_connect"))
    )
    (net (code "146") (name "unconnected-(Y300-NC-Pad2)") (class "Default")
      (node (ref "Y300") (pin "2") (pinfunction "NC_2") (pintype "passive+no_connect"))
    )
  )
)
